# mcu.net
KiCad netlist of a schematic drawn in Altium Designer
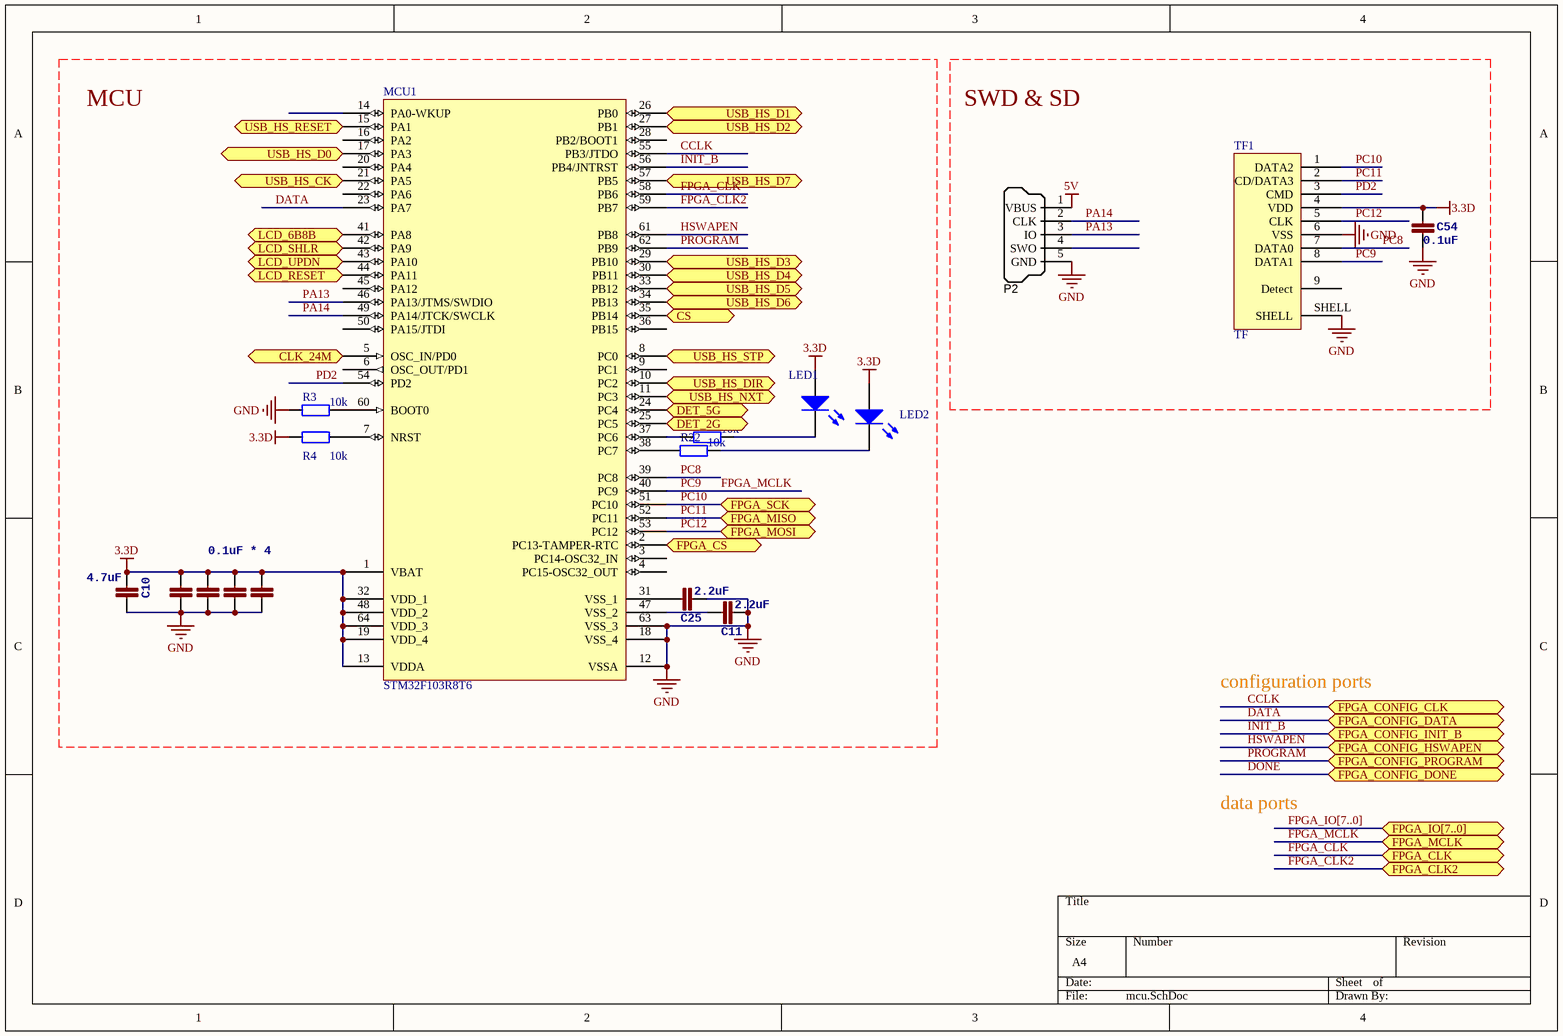
[diagram p0: mcu.SchDoc]

(export (version "E")
  (design (tool "Eeschema 10.0.6"))
  (components
    (comp (ref "C4")
      (value "0.1uF * 4")
      (footprint "0402")
      (description "<b>Capacitor</b>\nStandard 0603 ceramic capacitor, and 0.1\" leaded capacitor.")
      (fields (field (name "PARTNO") "CC0402ZRY5V7BB104"))
      (libsource (lib "*") (part "CAP0402-CAP"))
    )
    (comp (ref "C5")
      (value "1n")
      (footprint "0402")
      (description "<b>Capacitor</b>\nStandard 0603 ceramic capacitor, and 0.1\" leaded capacitor.")
      (fields (field (name "PARTNO") "CC0402ZRY5V7BB104"))
      (libsource (lib "pixhawk2") (part "CAP0402-CAP"))
    )
    (comp (ref "C6")
      (value "1n")
      (footprint "0402")
      (description "<b>Capacitor</b>\nStandard 0603 ceramic capacitor, and 0.1\" leaded capacitor.")
      (fields (field (name "PARTNO") "CC0402ZRY5V7BB104"))
      (libsource (lib "pixhawk2") (part "CAP0402-CAP"))
    )
    (comp (ref "C7")
      (value "1n")
      (footprint "0402")
      (description "<b>Capacitor</b>\nStandard 0603 ceramic capacitor, and 0.1\" leaded capacitor.")
      (fields (field (name "PARTNO") "CC0402ZRY5V7BB104"))
      (libsource (lib "pixhawk2") (part "CAP0402-CAP"))
    )
    (comp (ref "C10")
      (value "4.7uF")
      (footprint "0603")
      (description "<b>Capacitor</b>\nStandard 0603 ceramic capacitor, and 0.1\" leaded capacitor.")
      (fields (field (name "PARTNO") "CC0402ZRY5V7BB104"))
      (libsource (lib "pixhawk2") (part "CAP0402-CAP"))
    )
    (comp (ref "C11")
      (value "2.2uF")
      (footprint "0603")
      (description "<b>Capacitor</b>\nStandard 0603 ceramic capacitor, and 0.1\" leaded capacitor.")
      (fields (field (name "PARTNO") "CC0402ZRY5V7BB104"))
      (libsource (lib "") (part "CAP0402-CAP_1"))
    )
    (comp (ref "C25")
      (value "2.2uF")
      (footprint "0603")
      (description "<b>Capacitor</b>\nStandard 0603 ceramic capacitor, and 0.1\" leaded capacitor.")
      (fields (field (name "PARTNO") "CC0402ZRY5V7BB104"))
      (libsource (lib "") (part "CAP0402-CAP_1"))
    )
    (comp (ref "C54")
      (value "0.1uF")
      (footprint "0402")
      (description "<b>Capacitor</b>\nStandard 0603 ceramic capacitor, and 0.1\" leaded capacitor.")
      (fields (field (name "PARTNO") "CC0402ZRY5V7BB104"))
      (libsource (lib "pixhawk2") (part "CAP0402-CAP"))
    )
    (comp (ref "LED1")
      (value "LED0")
      (footprint "0603")
      (description "Typical INFRARED GaAs LED")
      (fields (field (name "PUBLISHER") "Altium Limited"))
      (libsource (lib "Miscellaneous Devices") (part "LED0"))
    )
    (comp (ref "LED2")
      (value "LED0")
      (footprint "0603")
      (description "Typical INFRARED GaAs LED")
      (fields (field (name "PUBLISHER") "Altium Limited"))
      (libsource (lib "Miscellaneous Devices") (part "LED0"))
    )
    (comp (ref "MCU1")
      (value "STM32F103R8T6")
      (footprint "LQFP64_N")
      (description "STM32 ARM-based 32-bit MCU with 64 Kbytes Flash, 64-pin LQFP, Industrial Temperature")
      (fields (field (name "PUBLISHER") "*"))
      (libsource (lib "ST Microcontroller 32-Bit STM32 SCH") (part "STM32F103R8T6"))
    )
    (comp (ref "P2")
      (value "SWD_MicroUSB")
      (footprint "MICRO-YZX")
      (description "Connector SMD USB Micro Type B middle mount")
      (libsource (lib "sch") (part "SWD_MicroUSB"))
    )
    (comp (ref "R3")
      (value "10k")
      (footprint "0402")
      (description "Resistor")
      (fields (field (name "PUBLISHER") "Altium Limited"))
      (libsource (lib "Miscellaneous Devices") (part "Res2"))
    )
    (comp (ref "R4")
      (value "10k")
      (footprint "0402")
      (description "Resistor")
      (fields (field (name "PUBLISHER") "Altium Limited"))
      (libsource (lib "") (part "Res2_1"))
    )
    (comp (ref "R21")
      (value "10k")
      (footprint "0402")
      (description "Resistor")
      (fields (field (name "PUBLISHER") "Altium Limited"))
      (libsource (lib "Miscellaneous Devices") (part "Res2"))
    )
    (comp (ref "R22")
      (value "10k")
      (footprint "0402")
      (description "Resistor")
      (fields (field (name "PUBLISHER") "Altium Limited"))
      (libsource (lib "Miscellaneous Devices") (part "Res2"))
    )
    (comp (ref "TF1") (value "TF") (footprint "TF") (libsource (lib "complements") (part "TF")))
  )
  (nets
    (net (code "9") (name "/CCLK") (class "Default")
      (node (ref "MCU1") (pin "55") (pinfunction "PB3/JTDO_55") (pintype "bidirectional"))
    )
    (net (code "10") (name "/CLK_24M") (class "Default")
      (node (ref "MCU1") (pin "5") (pinfunction "OSC_IN/PD0_5") (pintype "input"))
    )
    (net (code "11") (name "/CS") (class "Default")
      (node (ref "MCU1") (pin "35") (pinfunction "PB14_35") (pintype "bidirectional"))
    )
    (net (code "12") (name "/DATA") (class "Default")
      (node (ref "MCU1") (pin "23") (pinfunction "PA7_23") (pintype "bidirectional"))
    )
    (net (code "13") (name "/DET_2G") (class "Default")
      (node (ref "MCU1") (pin "25") (pinfunction "PC5_25") (pintype "bidirectional"))
    )
    (net (code "14") (name "/DET_5G") (class "Default")
      (node (ref "MCU1") (pin "24") (pinfunction "PC4_24") (pintype "bidirectional"))
    )
    (net (code "16") (name "/FPGA_CLK") (class "Default")
      (node (ref "MCU1") (pin "58") (pinfunction "PB6_58") (pintype "bidirectional"))
    )
    (net (code "17") (name "/FPGA_CLK2") (class "Default")
      (node (ref "MCU1") (pin "59") (pinfunction "PB7_59") (pintype "bidirectional"))
    )
    (net (code "18") (name "/FPGA_CS") (class "Default")
      (node (ref "MCU1") (pin "2") (pinfunction "PC13-TAMPER-RTC_2") (pintype "bidirectional"))
    )
    (net (code "20") (name "/FPGA_MCLK") (class "Default")
      (node (ref "MCU1") (pin "40") (pinfunction "PC9_40") (pintype "bidirectional"))
      (node (ref "TF1") (pin "8") (pinfunction "DATA1_8") (pintype "passive"))
    )
    (net (code "21") (name "/HSWAPEN") (class "Default")
      (node (ref "MCU1") (pin "61") (pinfunction "PB8_61") (pintype "bidirectional"))
    )
    (net (code "22") (name "/INIT_B") (class "Default")
      (node (ref "MCU1") (pin "56") (pinfunction "PB4/JNTRST_56") (pintype "bidirectional"))
    )
    (net (code "23") (name "/LCD_6B8B") (class "Default")
      (node (ref "MCU1") (pin "41") (pinfunction "PA8_41") (pintype "bidirectional"))
    )
    (net (code "24") (name "/LCD_RESET") (class "Default")
      (node (ref "MCU1") (pin "44") (pinfunction "PA11_44") (pintype "bidirectional"))
    )
    (net (code "25") (name "/LCD_SHLR") (class "Default")
      (node (ref "MCU1") (pin "42") (pinfunction "PA9_42") (pintype "bidirectional"))
    )
    (net (code "26") (name "/LCD_UPDN") (class "Default")
      (node (ref "MCU1") (pin "43") (pinfunction "PA10_43") (pintype "bidirectional"))
    )
    (net (code "27") (name "/PA13") (class "Default")
      (node (ref "MCU1") (pin "46") (pinfunction "PA13/JTMS/SWDIO_46") (pintype "bidirectional"))
      (node (ref "P2") (pin "3") (pinfunction "IO_3") (pintype "passive"))
    )
    (net (code "28") (name "/PA14") (class "Default")
      (node (ref "MCU1") (pin "49") (pinfunction "PA14/JTCK/SWCLK_49") (pintype "bidirectional"))
      (node (ref "P2") (pin "2") (pinfunction "CLK_2") (pintype "passive"))
    )
    (net (code "29") (name "/PC8") (class "Default")
      (node (ref "MCU1") (pin "39") (pinfunction "PC8_39") (pintype "bidirectional"))
      (node (ref "TF1") (pin "7") (pinfunction "DATA0_7") (pintype "passive"))
    )
    (net (code "30") (name "/PC10") (class "Default")
      (node (ref "MCU1") (pin "51") (pinfunction "PC10_51") (pintype "bidirectional"))
      (node (ref "TF1") (pin "1") (pinfunction "DATA2_1") (pintype "passive"))
    )
    (net (code "31") (name "/PC11") (class "Default")
      (node (ref "MCU1") (pin "52") (pinfunction "PC11_52") (pintype "bidirectional"))
      (node (ref "TF1") (pin "2") (pinfunction "CD/DATA3_2") (pintype "passive"))
    )
    (net (code "32") (name "/PC12") (class "Default")
      (node (ref "MCU1") (pin "53") (pinfunction "PC12_53") (pintype "bidirectional"))
      (node (ref "TF1") (pin "5") (pinfunction "CLK_5") (pintype "passive"))
    )
    (net (code "33") (name "/PD2") (class "Default")
      (node (ref "MCU1") (pin "54") (pinfunction "PD2_54") (pintype "bidirectional"))
      (node (ref "TF1") (pin "3") (pinfunction "CMD_3") (pintype "passive"))
    )
    (net (code "34") (name "/PROGRAM") (class "Default")
      (node (ref "MCU1") (pin "62") (pinfunction "PB9_62") (pintype "bidirectional"))
    )
    (net (code "35") (name "/USB_HS_CK") (class "Default")
      (node (ref "MCU1") (pin "21") (pinfunction "PA5_21") (pintype "bidirectional"))
    )
    (net (code "36") (name "/USB_HS_D0") (class "Default")
      (node (ref "MCU1") (pin "17") (pinfunction "PA3_17") (pintype "bidirectional"))
    )
    (net (code "37") (name "/USB_HS_D1") (class "Default")
      (node (ref "MCU1") (pin "26") (pinfunction "PB0_26") (pintype "bidirectional"))
    )
    (net (code "38") (name "/USB_HS_D2") (class "Default")
      (node (ref "MCU1") (pin "27") (pinfunction "PB1_27") (pintype "bidirectional"))
    )
    (net (code "39") (name "/USB_HS_D3") (class "Default")
      (node (ref "MCU1") (pin "29") (pinfunction "PB10_29") (pintype "bidirectional"))
    )
    (net (code "40") (name "/USB_HS_D4") (class "Default")
      (node (ref "MCU1") (pin "30") (pinfunction "PB11_30") (pintype "bidirectional"))
    )
    (net (code "41") (name "/USB_HS_D5") (class "Default")
      (node (ref "MCU1") (pin "33") (pinfunction "PB12_33") (pintype "bidirectional"))
    )
    (net (code "42") (name "/USB_HS_D6") (class "Default")
      (node (ref "MCU1") (pin "34") (pinfunction "PB13_34") (pintype "bidirectional"))
    )
    (net (code "43") (name "/USB_HS_D7") (class "Default")
      (node (ref "MCU1") (pin "57") (pinfunction "PB5_57") (pintype "bidirectional"))
    )
    (net (code "44") (name "/USB_HS_DIR") (class "Default")
      (node (ref "MCU1") (pin "10") (pinfunction "PC2_10") (pintype "bidirectional"))
    )
    (net (code "45") (name "/USB_HS_NXT") (class "Default")
      (node (ref "MCU1") (pin "11") (pinfunction "PC3_11") (pintype "bidirectional"))
    )
    (net (code "46") (name "/USB_HS_RESET") (class "Default")
      (node (ref "MCU1") (pin "15") (pinfunction "PA1_15") (pintype "bidirectional"))
    )
    (net (code "47") (name "/USB_HS_STP") (class "Default")
      (node (ref "MCU1") (pin "8") (pinfunction "PC0_8") (pintype "bidirectional"))
    )
    (net (code "48") (name "3.3D") (class "Default")
      (node (ref "C10") (pin "2") (pinfunction "2_2") (pintype "passive"))
      (node (ref "C4") (pin "2") (pinfunction "2_2") (pintype "passive"))
      (node (ref "C5") (pin "2") (pinfunction "2_2") (pintype "passive"))
      (node (ref "C54") (pin "2") (pinfunction "2_2") (pintype "passive"))
      (node (ref "C6") (pin "2") (pinfunction "2_2") (pintype "passive"))
      (node (ref "C7") (pin "2") (pinfunction "2_2") (pintype "passive"))
      (node (ref "LED1") (pin "1") (pinfunction "A_1") (pintype "passive"))
      (node (ref "LED2") (pin "1") (pinfunction "A_1") (pintype "passive"))
      (node (ref "MCU1") (pin "1") (pinfunction "VBAT_1") (pintype "power_in"))
      (node (ref "MCU1") (pin "13") (pinfunction "VDDA_13") (pintype "power_in"))
      (node (ref "MCU1") (pin "19") (pinfunction "VDD_4_19") (pintype "power_in"))
      (node (ref "MCU1") (pin "32") (pinfunction "VDD_1_32") (pintype "power_in"))
      (node (ref "MCU1") (pin "48") (pinfunction "VDD_2_48") (pintype "power_in"))
      (node (ref "MCU1") (pin "64") (pinfunction "VDD_3_64") (pintype "power_in"))
      (node (ref "R4") (pin "2") (pinfunction "2_2") (pintype "passive"))
      (node (ref "TF1") (pin "4") (pinfunction "VDD_4") (pintype "passive"))
    )
    (net (code "49") (name "5V") (class "Default")
      (node (ref "P2") (pin "1") (pinfunction "VBUS_1") (pintype "passive"))
    )
    (net (code "50") (name "GND") (class "Default")
      (node (ref "C10") (pin "1") (pinfunction "1_1") (pintype "passive"))
      (node (ref "C11") (pin "2") (pinfunction "2_2") (pintype "passive"))
      (node (ref "C25") (pin "2") (pinfunction "2_2") (pintype "passive"))
      (node (ref "C4") (pin "1") (pinfunction "1_1") (pintype "passive"))
      (node (ref "C5") (pin "1") (pinfunction "1_1") (pintype "passive"))
      (node (ref "C54") (pin "1") (pinfunction "1_1") (pintype "passive"))
      (node (ref "C6") (pin "1") (pinfunction "1_1") (pintype "passive"))
      (node (ref "C7") (pin "1") (pinfunction "1_1") (pintype "passive"))
      (node (ref "MCU1") (pin "12") (pinfunction "VSSA_12") (pintype "power_in"))
      (node (ref "MCU1") (pin "18") (pinfunction "VSS_4_18") (pintype "power_in"))
      (node (ref "MCU1") (pin "63") (pinfunction "VSS_3_63") (pintype "power_in"))
      (node (ref "P2") (pin "5") (pinfunction "GND_5") (pintype "passive"))
      (node (ref "R3") (pin "1") (pinfunction "1_1") (pintype "passive"))
      (node (ref "TF1") (pin "6") (pinfunction "VSS_6") (pintype "passive"))
      (node (ref "TF1") (pin "SHELL") (pinfunction "SHELL_SHELL") (pintype "passive"))
    )
    (net (code "51") (name "Net-(LED1-K)") (class "Default")
      (node (ref "LED1") (pin "2") (pinfunction "K_2") (pintype "passive"))
      (node (ref "R21") (pin "2") (pinfunction "2_2") (pintype "passive"))
    )
    (net (code "52") (name "Net-(LED2-K)") (class "Default")
      (node (ref "LED2") (pin "2") (pinfunction "K_2") (pintype "passive"))
      (node (ref "R22") (pin "2") (pinfunction "2_2") (pintype "passive"))
    )
    (net (code "53") (name "Net-(MCU1-BOOT0)") (class "Default")
      (node (ref "MCU1") (pin "60") (pinfunction "BOOT0_60") (pintype "input"))
      (node (ref "R3") (pin "2") (pinfunction "2_2") (pintype "passive"))
    )
    (net (code "54") (name "Net-(MCU1-NRST)") (class "Default")
      (node (ref "MCU1") (pin "7") (pinfunction "NRST_7") (pintype "bidirectional"))
      (node (ref "R4") (pin "1") (pinfunction "1_1") (pintype "passive"))
    )
    (net (code "55") (name "Net-(MCU1-PC6)") (class "Default")
      (node (ref "MCU1") (pin "37") (pinfunction "PC6_37") (pintype "bidirectional"))
      (node (ref "R21") (pin "1") (pinfunction "1_1") (pintype "passive"))
    )
    (net (code "56") (name "Net-(MCU1-PC7)") (class "Default")
      (node (ref "MCU1") (pin "38") (pinfunction "PC7_38") (pintype "bidirectional"))
      (node (ref "R22") (pin "1") (pinfunction "1_1") (pintype "passive"))
    )
    (net (code "57") (name "Net-(MCU1-VSS_1)") (class "Default")
      (node (ref "C25") (pin "1") (pinfunction "1_1") (pintype "passive"))
      (node (ref "MCU1") (pin "31") (pinfunction "VSS_1_31") (pintype "power_in"))
    )
    (net (code "58") (name "Net-(MCU1-VSS_2)") (class "Default")
      (node (ref "C11") (pin "1") (pinfunction "1_1") (pintype "passive"))
      (node (ref "MCU1") (pin "47") (pinfunction "VSS_2_47") (pintype "power_in"))
    )
    (net (code "59") (name "unconnected-(MCU1-OSC_OUT{slash}PD1-Pad6)") (class "Default")
      (node (ref "MCU1") (pin "6") (pinfunction "OSC_OUT/PD1_6") (pintype "output"))
    )
    (net (code "60") (name "unconnected-(MCU1-PA0-WKUP-Pad14)") (class "Default")
      (node (ref "MCU1") (pin "14") (pinfunction "PA0-WKUP_14") (pintype "bidirectional"))
    )
    (net (code "61") (name "unconnected-(MCU1-PA2-Pad16)") (class "Default")
      (node (ref "MCU1") (pin "16") (pinfunction "PA2_16") (pintype "bidirectional"))
    )
    (net (code "62") (name "unconnected-(MCU1-PA4-Pad20)") (class "Default")
      (node (ref "MCU1") (pin "20") (pinfunction "PA4_20") (pintype "bidirectional"))
    )
    (net (code "63") (name "unconnected-(MCU1-PA6-Pad22)") (class "Default")
      (node (ref "MCU1") (pin "22") (pinfunction "PA6_22") (pintype "bidirectional"))
    )
    (net (code "64") (name "unconnected-(MCU1-PA12-Pad45)") (class "Default")
      (node (ref "MCU1") (pin "45") (pinfunction "PA12_45") (pintype "bidirectional"))
    )
    (net (code "65") (name "unconnected-(MCU1-PA15{slash}JTDI-Pad50)") (class "Default")
      (node (ref "MCU1") (pin "50") (pinfunction "PA15/JTDI_50") (pintype "bidirectional"))
    )
    (net (code "66") (name "unconnected-(MCU1-PB2{slash}BOOT1-Pad28)") (class "Default")
      (node (ref "MCU1") (pin "28") (pinfunction "PB2/BOOT1_28") (pintype "bidirectional"))
    )
    (net (code "67") (name "unconnected-(MCU1-PB15-Pad36)") (class "Default")
      (node (ref "MCU1") (pin "36") (pinfunction "PB15_36") (pintype "bidirectional"))
    )
    (net (code "68") (name "unconnected-(MCU1-PC1-Pad9)") (class "Default")
      (node (ref "MCU1") (pin "9") (pinfunction "PC1_9") (pintype "bidirectional"))
    )
    (net (code "69") (name "unconnected-(MCU1-PC14-OSC32_IN-Pad3)") (class "Default")
      (node (ref "MCU1") (pin "3") (pinfunction "PC14-OSC32_IN_3") (pintype "bidirectional"))
    )
    (net (code "70") (name "unconnected-(MCU1-PC15-OSC32_OUT-Pad4)") (class "Default")
      (node (ref "MCU1") (pin "4") (pinfunction "PC15-OSC32_OUT_4") (pintype "bidirectional"))
    )
    (net (code "71") (name "unconnected-(P2-SWO-Pad4)") (class "Default")
      (node (ref "P2") (pin "4") (pinfunction "SWO_4") (pintype "passive"))
    )
    (net (code "72") (name "unconnected-(TF1-Detect-Pad9)") (class "Default")
      (node (ref "TF1") (pin "9") (pinfunction "Detect_9") (pintype "passive"))
    )
  )
)
